# LT8315_Test_Board.net
KiCad netlist of a schematic drawn in EAGLE
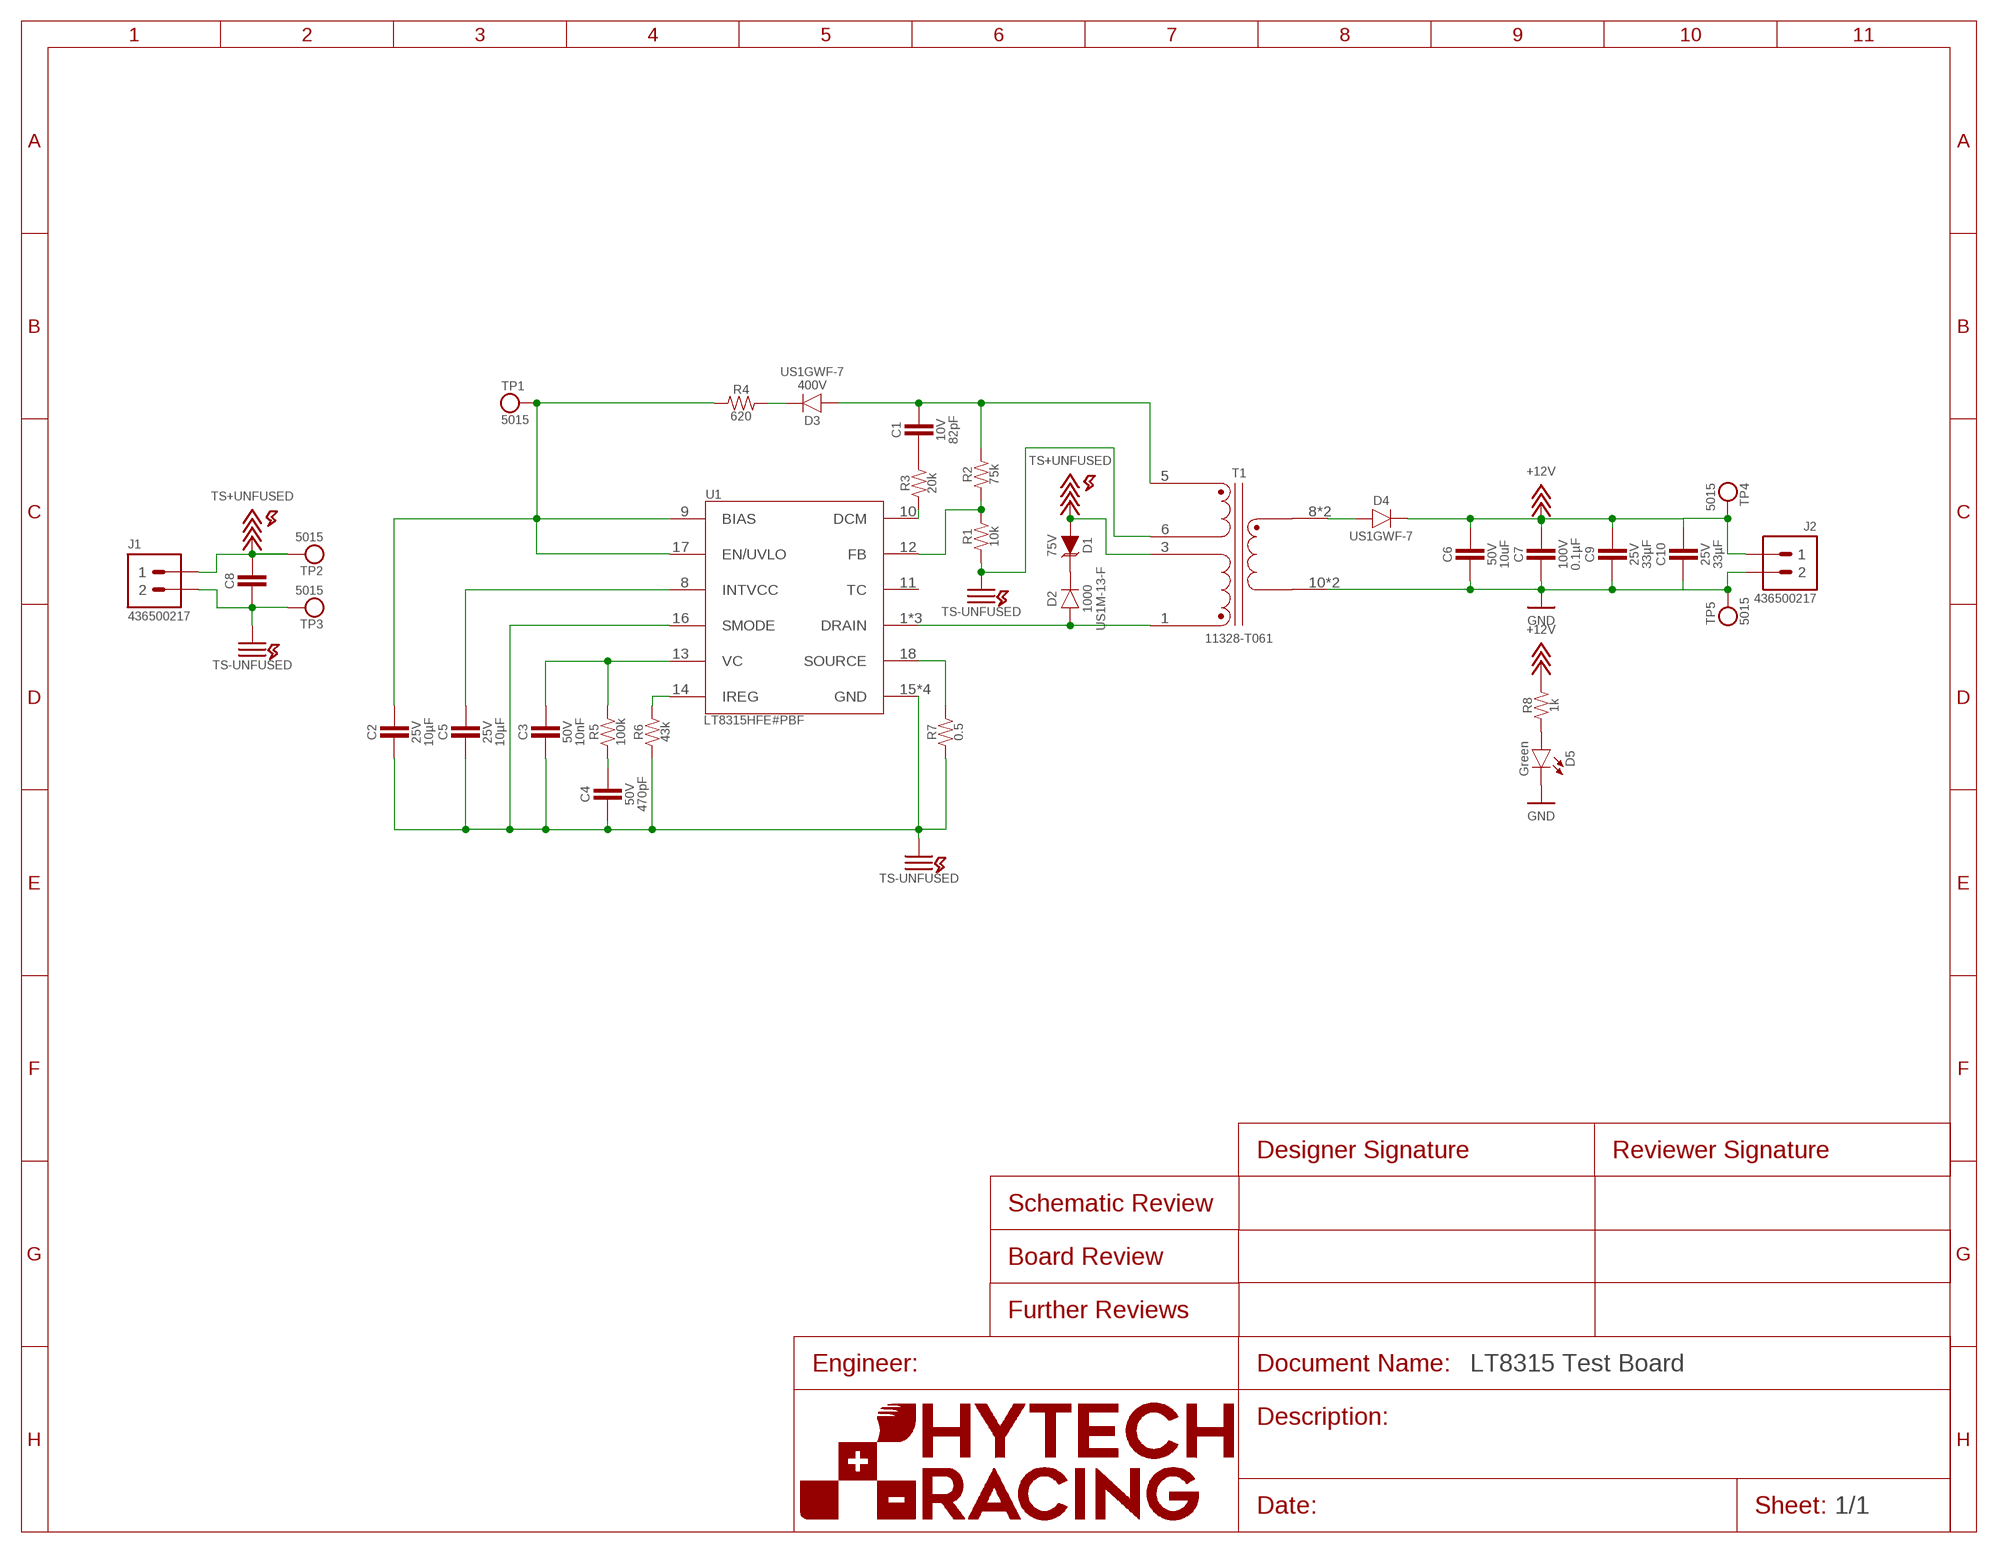
[diagram p0: schematic, sheet 1]

(export (version "E")
  (design (tool "Eeschema 10.0.6"))
  (components
    (comp (ref "C1")
      (value "CAPACITOR_0603_10V_82PF")
      (footprint "eagle-import:0603-CAP")
      (fields
        (field (name "CAPACITANCE") "82pF")
        (field (name "MANUFACTURER") "Kyocera AVX")
        (field (name "MPN") "0201ZA820JAT2A")
        (field (name "TOLERANCE") "5%")
        (field (name "VOLTAGE") "10V")
      )
      (libsource (lib "eagle-import") (part "CAPACITOR_?_060310V_82PF"))
    )
    (comp (ref "C2")
      (value "CAPACITOR_0603_25V_10UF")
      (footprint "eagle-import:0603-CAP")
      (fields
        (field (name "CAPACITANCE") "10µF")
        (field (name "MANUFACTURER") "Murata Electronics")
        (field (name "MPN") "GRM188R61E106MA73D")
        (field (name "TOLERANCE") "20%")
        (field (name "VOLTAGE") "25V")
      )
      (libsource (lib "eagle-import") (part "CAPACITOR_?_060325V_10UF"))
    )
    (comp (ref "C3")
      (value "CAPACITOR_0603_50V_10NF")
      (footprint "eagle-import:0603-CAP")
      (fields
        (field (name "CAPACITANCE") "10nF")
        (field (name "MANUFACTURER") "TDK Corporation")
        (field (name "MPN") "C1608C0G1H103J080AA")
        (field (name "TOLERANCE") "5%")
        (field (name "VOLTAGE") "50V")
      )
      (libsource (lib "eagle-import") (part "CAPACITOR_?_060350V_10NF"))
    )
    (comp (ref "C4")
      (value "CAPACITOR_0603_50V_470PF")
      (footprint "eagle-import:0603-CAP")
      (fields
        (field (name "CAPACITANCE") "470pF")
        (field (name "MANUFACTURER") "Samsung Electro-Mechanics")
        (field (name "MPN") "CL10B471JB8NNNC")
        (field (name "TOLERANCE") "5%")
        (field (name "VOLTAGE") "50V")
      )
      (libsource (lib "eagle-import") (part "CAPACITOR_?_060350V_470PF"))
    )
    (comp (ref "C5")
      (value "CAPACITOR_0603_25V_10UF")
      (footprint "eagle-import:0603-CAP")
      (fields
        (field (name "CAPACITANCE") "10µF")
        (field (name "MANUFACTURER") "Murata Electronics")
        (field (name "MPN") "GRM188R61E106MA73D")
        (field (name "TOLERANCE") "20%")
        (field (name "VOLTAGE") "25V")
      )
      (libsource (lib "eagle-import") (part "CAPACITOR_?_060325V_10UF"))
    )
    (comp (ref "C6")
      (value "CAPACITOR_0805_50V_10UF")
      (footprint "eagle-import:0805-CAP")
      (fields
        (field (name "CAPACITANCE") "10uF")
        (field (name "MANUFACTURER") "Murata")
        (field (name "MPN") " GRM21BR61H106KE43L")
        (field (name "TOLERANCE") "10%")
        (field (name "VOLTAGE") "50V")
      )
      (libsource (lib "eagle-import") (part "CAPACITOR_?_080550V_10UF"))
    )
    (comp (ref "C7")
      (value "CAPACITOR_0603_100V_0.1UF")
      (footprint "eagle-import:0603-CAP")
      (fields
        (field (name "CAPACITANCE") "0.1µF")
        (field (name "MANUFACTURER") "Yageo")
        (field (name "MPN") "CC0603KRX7R0BB104")
        (field (name "TOLERANCE") "10%")
        (field (name "VOLTAGE") "100V")
      )
      (libsource (lib "eagle-import") (part "CAPACITOR_?_0603100V_0.1UF"))
    )
    (comp (ref "C8")
      (value "CAPACITOR__0.1UF")
      (footprint "eagle-import:1812-CAP")
      (fields (field (name "MANUFACTURER") "KEMET") (field (name "MPN") "C1812W104KDRAC7800"))
      (libsource (lib "eagle-import") (part "CAPACITOR_?_0.1UF"))
    )
    (comp (ref "C9")
      (value "CAPACITOR_1206_25V_33UF")
      (footprint "eagle-import:1206-CAP")
      (fields
        (field (name "CAPACITANCE") "33µF")
        (field (name "MANUFACTURER") "TDK Corporation")
        (field (name "MPN") "C3216X5R1E336M160AC")
        (field (name "TOLERANCE") "20%")
        (field (name "VOLTAGE") "25V")
      )
      (libsource (lib "eagle-import") (part "CAPACITOR_?_120625V_33UF"))
    )
    (comp (ref "C10")
      (value "CAPACITOR_1206_25V_33UF")
      (footprint "eagle-import:1206-CAP")
      (fields
        (field (name "CAPACITANCE") "33µF")
        (field (name "MANUFACTURER") "TDK Corporation")
        (field (name "MPN") "C3216X5R1E336M160AC")
        (field (name "TOLERANCE") "20%")
        (field (name "VOLTAGE") "25V")
      )
      (libsource (lib "eagle-import") (part "CAPACITOR_?_120625V_33UF"))
    )
    (comp (ref "D1")
      (value "TVS_SOD323F")
      (footprint "eagle-import:SOD323F")
      (fields
        (field (name "VOLTAGE") "75V")
        (field (name "MANUFACTURER") "ONSEMI")
        (field (name "MPN") "MM3Z75VB")
      )
      (libsource (lib "eagle-import") (part "TVS_SOD323F"))
    )
    (comp (ref "D2")
      (value "RECTIFIER__SMA")
      (footprint "eagle-import:SMA")
      (fields
        (field (name "VOLTAGE") "1000")
        (field (name "MPN") "US1M-13-F")
        (field (name "MANUFACTURER") "Diodes Incorporated")
      )
      (libsource (lib "eagle-import") (part "RECTIFIER__?SMA"))
    )
    (comp (ref "D3")
      (value "RECTIFIER_400V_SOD123")
      (footprint "eagle-import:SOD123F")
      (fields
        (field (name "MANUFACTURER") "Diodes Incorporated")
        (field (name "MPN") "US1GWF-7")
        (field (name "VOLTAGE") "400V")
      )
      (libsource (lib "eagle-import") (part "RECTIFIER__?SOD123400V"))
    )
    (comp (ref "D4")
      (value "RECTIFIER_400V_SOD123")
      (footprint "eagle-import:SOD123F")
      (fields
        (field (name "MANUFACTURER") "Diodes Incorporated")
        (field (name "MPN") "US1GWF-7")
        (field (name "VOLTAGE") "400V")
      )
      (libsource (lib "eagle-import") (part "RECTIFIER__?SOD123400V"))
    )
    (comp (ref "D5")
      (value "LED_0603_GREEN")
      (footprint "eagle-import:0603-LED")
      (fields
        (field (name "COLOR") "Green")
        (field (name "MANUFACTURER") "Kingbright")
        (field (name "MPN") "APT1608ZGCK")
      )
      (libsource (lib "eagle-import") (part "LED_?_0603GREEN"))
    )
    (comp (ref "J1")
      (value "CONNECTOR-2_μF_T_V_BLACK")
      (footprint "eagle-import:MOLEX_MICROFIT_PTH_VERTICAL_02_DUAL")
      (fields (field (name "MANUFACTURER") "Molex") (field (name "MPN") "436500217"))
      (libsource (lib "eagle-import") (part "CONNECTOR-2_?_μF_T_VBLACK"))
    )
    (comp (ref "J2")
      (value "CONNECTOR-2_μF_T_V_BLACK")
      (footprint "eagle-import:MOLEX_MICROFIT_PTH_VERTICAL_02_DUAL")
      (fields (field (name "MANUFACTURER") "Molex") (field (name "MPN") "436500217"))
      (libsource (lib "eagle-import") (part "CONNECTOR-2_?_μF_T_VBLACK"))
    )
    (comp (ref "R1")
      (value "RESISTOR_0603_10K")
      (footprint "eagle-import:0603-RES")
      (fields
        (field (name "MANUFACTURER") "Yageo")
        (field (name "MPN") "RC0603FR-0710KL")
        (field (name "POWER") "0.1W")
        (field (name "RESISTANCE") "10k")
      )
      (libsource (lib "eagle-import") (part "RESISTOR_?_060310K"))
    )
    (comp (ref "R2")
      (value "RESISTOR_0603_75K")
      (footprint "eagle-import:0603-RES")
      (fields
        (field (name "MANUFACTURER") "Yageo")
        (field (name "MPN") "RT0603BRE0775KL")
        (field (name "POWER") "0.1W")
        (field (name "RESISTANCE") "75k")
      )
      (libsource (lib "eagle-import") (part "RESISTOR_?_060375K"))
    )
    (comp (ref "R3")
      (value "RESISTOR_0603_20K")
      (footprint "eagle-import:0603-RES")
      (fields
        (field (name "MANUFACTURER") "Yageo")
        (field (name "MPN") "RC0603FR-0720KL")
        (field (name "POWER") "0.1 W")
        (field (name "RESISTANCE") "20k")
      )
      (libsource (lib "eagle-import") (part "RESISTOR_?_060320K"))
    )
    (comp (ref "R4")
      (value "RESISTOR_0603_620")
      (footprint "eagle-import:0603-RES")
      (fields
        (field (name "MANUFACTURER") "Yageo")
        (field (name "MPN") "RC0603FR-07620RL")
        (field (name "POWER") "0.1W")
        (field (name "RESISTANCE") "620")
      )
      (libsource (lib "eagle-import") (part "RESISTOR_?_0603620"))
    )
    (comp (ref "R5")
      (value "RESISTOR_0603_100K")
      (footprint "eagle-import:0603-RES")
      (fields
        (field (name "MANUFACTURER") "Yageo")
        (field (name "MPN") "RC0603FR-07100KL")
        (field (name "POWER") "0.1W")
        (field (name "RESISTANCE") "100k")
      )
      (libsource (lib "eagle-import") (part "RESISTOR_?_0603100K"))
    )
    (comp (ref "R6")
      (value "RESISTOR_0603_43K")
      (footprint "eagle-import:0603-RES")
      (fields
        (field (name "MANUFACTURER") "Yageo")
        (field (name "MPN") "RC0603FR-0743KL")
        (field (name "POWER") "0.1W")
        (field (name "RESISTANCE") "43k")
      )
      (libsource (lib "eagle-import") (part "RESISTOR_?_060343K"))
    )
    (comp (ref "R7")
      (value "RESISTOR_0603_0.5")
      (footprint "eagle-import:0603-RES")
      (fields
        (field (name "MANUFACTURER") "Yageo")
        (field (name "MPN") "RL0603FR-070R5L")
        (field (name "POWER") "0.1W")
        (field (name "RESISTANCE") "0.5")
      )
      (libsource (lib "eagle-import") (part "RESISTOR_?_06030.5"))
    )
    (comp (ref "R8")
      (value "RESISTOR_0603_1K")
      (footprint "eagle-import:0603-RES")
      (fields
        (field (name "MANUFACTURER") "TE Connectivity Passive Product")
        (field (name "MPN") " CPF-A-0603B1K0E")
        (field (name "POWER") "0.0625W")
        (field (name "RESISTANCE") "1k")
      )
      (libsource (lib "eagle-import") (part "RESISTOR_?_06031K"))
    )
    (comp (ref "T1")
      (value "TRANSFORMER(3W)")
      (footprint "eagle-import:PQ2620")
      (fields (field (name "MPN") "11328-T061") (field (name "MANUFACTURER") "Sumida"))
      (libsource (lib "eagle-import") (part "TRANSFORMER(3W)"))
    )
    (comp (ref "TP1")
      (value "TEST_POINT")
      (footprint "eagle-import:5015")
      (fields (field (name "MPN") "5015") (field (name "MANUFACTURER") "Keystone Electronics"))
      (libsource (lib "eagle-import") (part "TEST_POINT"))
    )
    (comp (ref "TP2")
      (value "TEST_POINT")
      (footprint "eagle-import:5015")
      (fields (field (name "MPN") "5015") (field (name "MANUFACTURER") "Keystone Electronics"))
      (libsource (lib "eagle-import") (part "TEST_POINT"))
    )
    (comp (ref "TP3")
      (value "TEST_POINT")
      (footprint "eagle-import:5015")
      (fields (field (name "MPN") "5015") (field (name "MANUFACTURER") "Keystone Electronics"))
      (libsource (lib "eagle-import") (part "TEST_POINT"))
    )
    (comp (ref "TP4")
      (value "TEST_POINT")
      (footprint "eagle-import:5015")
      (fields (field (name "MPN") "5015") (field (name "MANUFACTURER") "Keystone Electronics"))
      (libsource (lib "eagle-import") (part "TEST_POINT"))
    )
    (comp (ref "TP5")
      (value "TEST_POINT")
      (footprint "eagle-import:5015")
      (fields (field (name "MPN") "5015") (field (name "MANUFACTURER") "Keystone Electronics"))
      (libsource (lib "eagle-import") (part "TEST_POINT"))
    )
    (comp (ref "U1")
      (value "LT8315")
      (footprint "eagle-import:TSSP-20(16)")
      (fields (field (name "MPN") "LT8315HFE#PBF") (field (name "MANUFACTURER") "Analog Devices"))
      (libsource (lib "eagle-import") (part "LT8315"))
    )
  )
  (nets
    (net (code "1") (name "+12V") (class "Default")
      (node (ref "C10") (pin "1") (pinfunction "1_1") (pintype "passive"))
      (node (ref "C6") (pin "1") (pinfunction "1_1") (pintype "passive"))
      (node (ref "C7") (pin "1") (pinfunction "1_1") (pintype "passive"))
      (node (ref "C9") (pin "1") (pinfunction "1_1") (pintype "passive"))
      (node (ref "D4") (pin "C") (pinfunction "C_C") (pintype "passive"))
      (node (ref "J2") (pin "1") (pinfunction "1_1") (pintype "passive"))
      (node (ref "R8") (pin "2") (pinfunction "2_2") (pintype "passive"))
      (node (ref "TP4") (pin "1") (pinfunction "1_1") (pintype "passive"))
    )
    (net (code "2") (name "GND") (class "Default")
      (node (ref "C10") (pin "2") (pinfunction "2_2") (pintype "passive"))
      (node (ref "C6") (pin "2") (pinfunction "2_2") (pintype "passive"))
      (node (ref "C7") (pin "2") (pinfunction "2_2") (pintype "passive"))
      (node (ref "C9") (pin "2") (pinfunction "2_2") (pintype "passive"))
      (node (ref "D5") (pin "1") (pinfunction "C_1") (pintype "passive"))
      (node (ref "J2") (pin "2") (pinfunction "2_2") (pintype "passive"))
      (node (ref "T1") (pin "10") (pinfunction "10,11_10") (pintype "bidirectional"))
      (node (ref "T1") (pin "11") (pinfunction "10,11_11") (pintype "bidirectional"))
      (node (ref "TP5") (pin "1") (pinfunction "1_1") (pintype "passive"))
    )
    (net (code "3") (name "Net-(C1-Pad1)") (class "Default")
      (node (ref "C1") (pin "1") (pinfunction "1_1") (pintype "passive"))
      (node (ref "D3") (pin "A") (pinfunction "A_A") (pintype "passive"))
      (node (ref "R2") (pin "2") (pinfunction "2_2") (pintype "passive"))
      (node (ref "T1") (pin "5") (pinfunction "5_5") (pintype "bidirectional"))
    )
    (net (code "4") (name "Net-(C1-Pad2)") (class "Default")
      (node (ref "C1") (pin "2") (pinfunction "2_2") (pintype "passive"))
      (node (ref "R3") (pin "2") (pinfunction "2_2") (pintype "passive"))
    )
    (net (code "5") (name "Net-(C4-Pad1)") (class "Default")
      (node (ref "C4") (pin "1") (pinfunction "1_1") (pintype "passive"))
      (node (ref "R5") (pin "1") (pinfunction "1_1") (pintype "passive"))
    )
    (net (code "6") (name "Net-(D1-PadC)") (class "Default")
      (node (ref "D1") (pin "C") (pinfunction "C_C") (pintype "passive"))
      (node (ref "D2") (pin "C") (pinfunction "C_C") (pintype "passive"))
    )
    (net (code "7") (name "Net-(D2-PadA)") (class "Default")
      (node (ref "D2") (pin "A") (pinfunction "A_A") (pintype "passive"))
      (node (ref "T1") (pin "1") (pinfunction "1_1") (pintype "bidirectional"))
      (node (ref "U1") (pin "1") (pinfunction "DRAIN_1") (pintype "bidirectional"))
      (node (ref "U1") (pin "2") (pinfunction "DRAIN_2") (pintype "bidirectional"))
      (node (ref "U1") (pin "3") (pinfunction "DRAIN_3") (pintype "bidirectional"))
    )
    (net (code "8") (name "Net-(D3-PadC)") (class "Default")
      (node (ref "D3") (pin "C") (pinfunction "C_C") (pintype "passive"))
      (node (ref "R4") (pin "2") (pinfunction "2_2") (pintype "passive"))
    )
    (net (code "9") (name "Net-(D4-PadA)") (class "Default")
      (node (ref "D4") (pin "A") (pinfunction "A_A") (pintype "passive"))
      (node (ref "T1") (pin "8") (pinfunction "8,9_8") (pintype "bidirectional"))
      (node (ref "T1") (pin "9") (pinfunction "8,9_9") (pintype "bidirectional"))
    )
    (net (code "10") (name "Net-(D5-A)") (class "Default")
      (node (ref "D5") (pin "2") (pinfunction "A_2") (pintype "passive"))
      (node (ref "R8") (pin "1") (pinfunction "1_1") (pintype "passive"))
    )
    (net (code "11") (name "Net-(U1-BIAS)") (class "Default")
      (node (ref "C2") (pin "1") (pinfunction "1_1") (pintype "passive"))
      (node (ref "R4") (pin "1") (pinfunction "1_1") (pintype "passive"))
      (node (ref "TP1") (pin "1") (pinfunction "1_1") (pintype "passive"))
      (node (ref "U1") (pin "17") (pinfunction "EN/UVLO_17") (pintype "bidirectional"))
      (node (ref "U1") (pin "9") (pinfunction "BIAS_9") (pintype "bidirectional"))
    )
    (net (code "12") (name "Net-(U1-DCM)") (class "Default")
      (node (ref "R3") (pin "1") (pinfunction "1_1") (pintype "passive"))
      (node (ref "U1") (pin "10") (pinfunction "DCM_10") (pintype "bidirectional"))
    )
    (net (code "13") (name "Net-(U1-FB)") (class "Default")
      (node (ref "R1") (pin "2") (pinfunction "2_2") (pintype "passive"))
      (node (ref "R2") (pin "1") (pinfunction "1_1") (pintype "passive"))
      (node (ref "U1") (pin "12") (pinfunction "FB_12") (pintype "bidirectional"))
    )
    (net (code "14") (name "Net-(U1-INTVCC)") (class "Default")
      (node (ref "C5") (pin "1") (pinfunction "1_1") (pintype "passive"))
      (node (ref "U1") (pin "8") (pinfunction "INTVCC_8") (pintype "bidirectional"))
    )
    (net (code "15") (name "Net-(U1-IREG)") (class "Default")
      (node (ref "R6") (pin "2") (pinfunction "2_2") (pintype "passive"))
      (node (ref "U1") (pin "14") (pinfunction "IREG_14") (pintype "bidirectional"))
    )
    (net (code "16") (name "Net-(U1-SOURCE)") (class "Default")
      (node (ref "R7") (pin "2") (pinfunction "2_2") (pintype "passive"))
      (node (ref "U1") (pin "18") (pinfunction "SOURCE_18") (pintype "bidirectional"))
    )
    (net (code "17") (name "Net-(U1-VC)") (class "Default")
      (node (ref "C3") (pin "1") (pinfunction "1_1") (pintype "passive"))
      (node (ref "R5") (pin "2") (pinfunction "2_2") (pintype "passive"))
      (node (ref "U1") (pin "13") (pinfunction "VC_13") (pintype "bidirectional"))
    )
    (net (code "18") (name "TS+UNFUSED") (class "Default")
      (node (ref "C8") (pin "1") (pinfunction "1_1") (pintype "passive"))
      (node (ref "D1") (pin "A") (pinfunction "A_A") (pintype "passive"))
      (node (ref "J1") (pin "1") (pinfunction "1_1") (pintype "passive"))
      (node (ref "T1") (pin "3") (pinfunction "3_3") (pintype "bidirectional"))
      (node (ref "TP2") (pin "1") (pinfunction "1_1") (pintype "passive"))
    )
    (net (code "19") (name "TS-UNFUSED") (class "Default")
      (node (ref "C2") (pin "2") (pinfunction "2_2") (pintype "passive"))
      (node (ref "C3") (pin "2") (pinfunction "2_2") (pintype "passive"))
      (node (ref "C4") (pin "2") (pinfunction "2_2") (pintype "passive"))
      (node (ref "C5") (pin "2") (pinfunction "2_2") (pintype "passive"))
      (node (ref "C8") (pin "2") (pinfunction "2_2") (pintype "passive"))
      (node (ref "J1") (pin "2") (pinfunction "2_2") (pintype "passive"))
      (node (ref "R1") (pin "1") (pinfunction "1_1") (pintype "passive"))
      (node (ref "R6") (pin "1") (pinfunction "1_1") (pintype "passive"))
      (node (ref "R7") (pin "1") (pinfunction "1_1") (pintype "passive"))
      (node (ref "T1") (pin "6") (pinfunction "6_6") (pintype "bidirectional"))
      (node (ref "TP3") (pin "1") (pinfunction "1_1") (pintype "passive"))
      (node (ref "U1") (pin "15") (pinfunction "GND_15") (pintype "bidirectional"))
      (node (ref "U1") (pin "16") (pinfunction "SMODE_16") (pintype "bidirectional"))
      (node (ref "U1") (pin "19") (pinfunction "GND_19") (pintype "bidirectional"))
      (node (ref "U1") (pin "20") (pinfunction "GND_20") (pintype "bidirectional"))
      (node (ref "U1") (pin "P$1") (pinfunction "GND_P$1") (pintype "bidirectional"))
    )
    (net (code "20") (name "unconnected-(U1-TC-Pad11)") (class "Default")
      (node (ref "U1") (pin "11") (pinfunction "TC_11") (pintype "bidirectional"))
    )
  )
)
